# power.net
KiCad netlist of a schematic drawn in Altium Designer
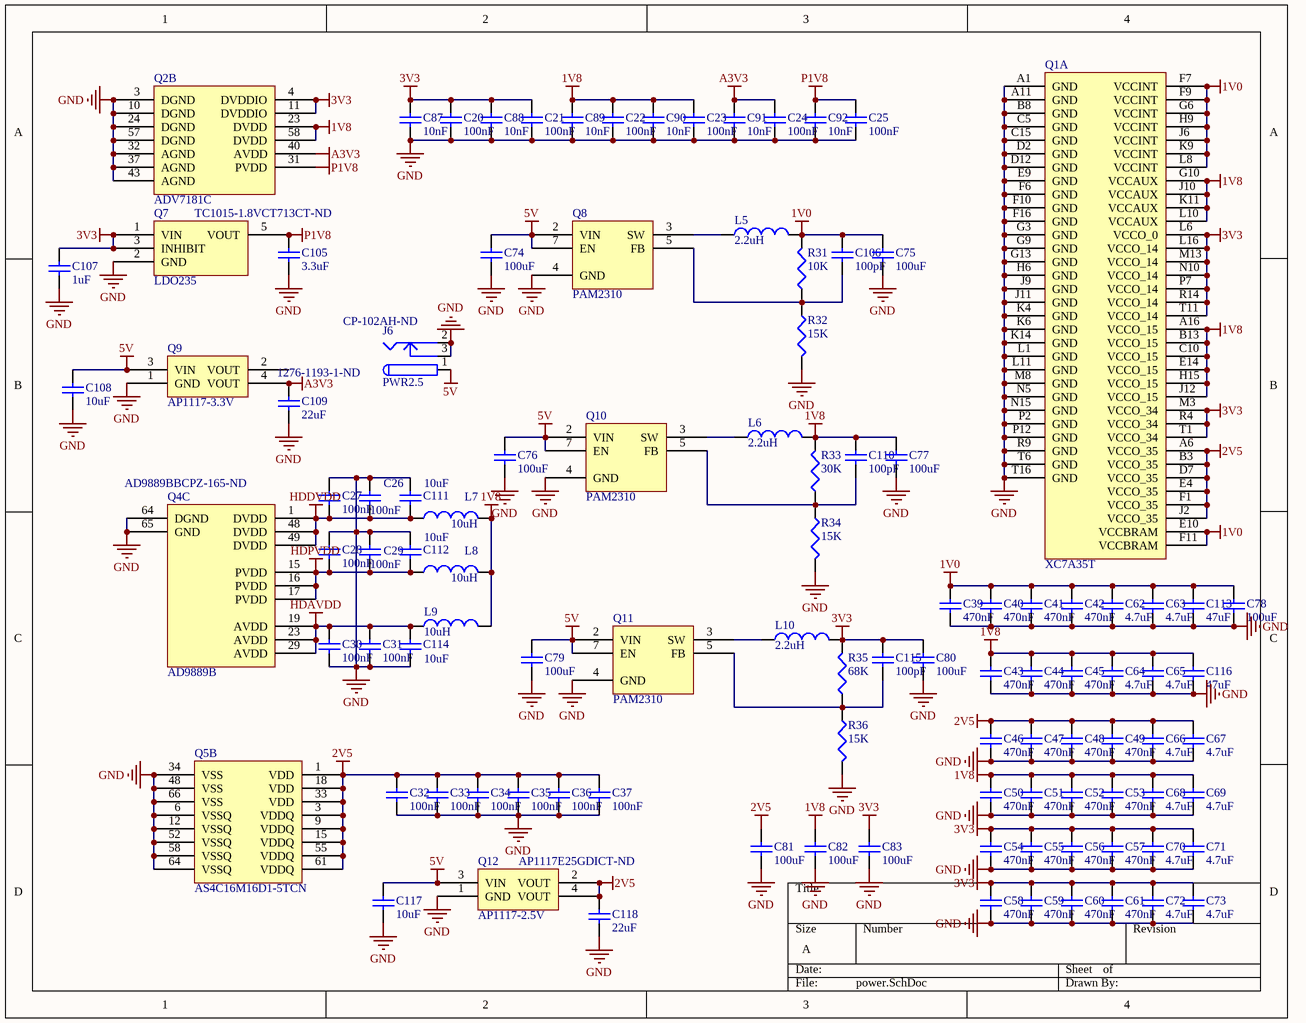
[diagram p0: power.SchDoc]

(export (version "E")
  (design (tool "Eeschema 10.0.6"))
  (components
    (comp (ref "C20")
      (value "100nF")
      (footprint "CAPC1005X06L")
      (description "Capacitor")
      (fields (field (name "Comment") "Cap") (field (name "PUBLISHER") "Altium Limited"))
      (libsource (lib "Miscellaneous Devices") (part "Cap"))
    )
    (comp (ref "C21")
      (value "100nF")
      (footprint "CAPC1005X06L")
      (description "Capacitor")
      (fields (field (name "Comment") "Cap") (field (name "PUBLISHER") "Altium Limited"))
      (libsource (lib "Miscellaneous Devices") (part "Cap"))
    )
    (comp (ref "C22")
      (value "100nF")
      (footprint "CAPC1005X06L")
      (description "Capacitor")
      (fields (field (name "Comment") "Cap") (field (name "PUBLISHER") "Altium Limited"))
      (libsource (lib "Miscellaneous Devices") (part "Cap"))
    )
    (comp (ref "C23")
      (value "100nF")
      (footprint "CAPC1005X06L")
      (description "Capacitor")
      (fields (field (name "Comment") "Cap") (field (name "PUBLISHER") "Altium Limited"))
      (libsource (lib "Miscellaneous Devices") (part "Cap"))
    )
    (comp (ref "C24")
      (value "100nF")
      (footprint "CAPC1005X06L")
      (description "Capacitor")
      (fields (field (name "Comment") "Cap") (field (name "PUBLISHER") "Altium Limited"))
      (libsource (lib "Miscellaneous Devices") (part "Cap"))
    )
    (comp (ref "C25")
      (value "100nF")
      (footprint "CAPC1005X06L")
      (description "Capacitor")
      (fields (field (name "Comment") "Cap") (field (name "PUBLISHER") "Altium Limited"))
      (libsource (lib "Miscellaneous Devices") (part "Cap"))
    )
    (comp (ref "C26")
      (value "100nF")
      (footprint "CAPC1005X06L")
      (description "Capacitor")
      (fields (field (name "Comment") "Cap") (field (name "PUBLISHER") "Altium Limited"))
      (libsource (lib "Miscellaneous Devices") (part "Cap"))
    )
    (comp (ref "C27")
      (value "100nF")
      (footprint "CAPC1005X06L")
      (description "Capacitor")
      (fields (field (name "Comment") "Cap") (field (name "PUBLISHER") "Altium Limited"))
      (libsource (lib "Miscellaneous Devices") (part "Cap"))
    )
    (comp (ref "C28")
      (value "100nF")
      (footprint "CAPC1005X06L")
      (description "Capacitor")
      (fields (field (name "Comment") "Cap") (field (name "PUBLISHER") "Altium Limited"))
      (libsource (lib "Miscellaneous Devices") (part "Cap"))
    )
    (comp (ref "C29")
      (value "100nF")
      (footprint "CAPC1005X06L")
      (description "Capacitor")
      (fields (field (name "Comment") "Cap") (field (name "PUBLISHER") "Altium Limited"))
      (libsource (lib "Miscellaneous Devices") (part "Cap"))
    )
    (comp (ref "C30")
      (value "100nF")
      (footprint "CAPC1005X06L")
      (description "Capacitor")
      (fields (field (name "Comment") "Cap") (field (name "PUBLISHER") "Altium Limited"))
      (libsource (lib "Miscellaneous Devices") (part "Cap"))
    )
    (comp (ref "C31")
      (value "100nF")
      (footprint "CAPC1005X06L")
      (description "Capacitor")
      (fields (field (name "Comment") "Cap") (field (name "PUBLISHER") "Altium Limited"))
      (libsource (lib "Miscellaneous Devices") (part "Cap"))
    )
    (comp (ref "C32")
      (value "100nF")
      (footprint "CAPC1005X06L")
      (description "Capacitor")
      (fields (field (name "Comment") "Cap") (field (name "PUBLISHER") "Altium Limited"))
      (libsource (lib "Miscellaneous Devices") (part "Cap"))
    )
    (comp (ref "C33")
      (value "100nF")
      (footprint "CAPC1005X06L")
      (description "Capacitor")
      (fields (field (name "Comment") "Cap") (field (name "PUBLISHER") "Altium Limited"))
      (libsource (lib "Miscellaneous Devices") (part "Cap"))
    )
    (comp (ref "C34")
      (value "100nF")
      (footprint "CAPC1005X06L")
      (description "Capacitor")
      (fields (field (name "Comment") "Cap") (field (name "PUBLISHER") "Altium Limited"))
      (libsource (lib "Miscellaneous Devices") (part "Cap"))
    )
    (comp (ref "C35")
      (value "100nF")
      (footprint "CAPC1005X06L")
      (description "Capacitor")
      (fields (field (name "Comment") "Cap") (field (name "PUBLISHER") "Altium Limited"))
      (libsource (lib "Miscellaneous Devices") (part "Cap"))
    )
    (comp (ref "C36")
      (value "100nF")
      (footprint "CAPC1005X06L")
      (description "Capacitor")
      (fields (field (name "Comment") "Cap") (field (name "PUBLISHER") "Altium Limited"))
      (libsource (lib "Miscellaneous Devices") (part "Cap"))
    )
    (comp (ref "C37")
      (value "100nF")
      (footprint "CAPC1005X06L")
      (description "Capacitor")
      (fields (field (name "Comment") "Cap") (field (name "PUBLISHER") "Altium Limited"))
      (libsource (lib "Miscellaneous Devices") (part "Cap"))
    )
    (comp (ref "C39")
      (value "470nF")
      (footprint "CAPC1005X06L")
      (description "Capacitor")
      (fields (field (name "Comment") "Cap") (field (name "PUBLISHER") "Altium Limited"))
      (libsource (lib "Miscellaneous Devices") (part "Cap"))
    )
    (comp (ref "C40")
      (value "470nF")
      (footprint "CAPC1005X06L")
      (description "Capacitor")
      (fields (field (name "Comment") "Cap") (field (name "PUBLISHER") "Altium Limited"))
      (libsource (lib "Miscellaneous Devices") (part "Cap"))
    )
    (comp (ref "C41")
      (value "470nF")
      (footprint "CAPC1005X06L")
      (description "Capacitor")
      (fields (field (name "Comment") "Cap") (field (name "PUBLISHER") "Altium Limited"))
      (libsource (lib "Miscellaneous Devices") (part "Cap"))
    )
    (comp (ref "C42")
      (value "470nF")
      (footprint "CAPC1005X06L")
      (description "Capacitor")
      (fields (field (name "Comment") "Cap") (field (name "PUBLISHER") "Altium Limited"))
      (libsource (lib "Miscellaneous Devices") (part "Cap"))
    )
    (comp (ref "C43")
      (value "470nF")
      (footprint "CAPC1005X06L")
      (description "Capacitor")
      (fields (field (name "Comment") "Cap") (field (name "PUBLISHER") "Altium Limited"))
      (libsource (lib "Miscellaneous Devices") (part "Cap"))
    )
    (comp (ref "C44")
      (value "470nF")
      (footprint "CAPC1005X06L")
      (description "Capacitor")
      (fields (field (name "Comment") "Cap") (field (name "PUBLISHER") "Altium Limited"))
      (libsource (lib "Miscellaneous Devices") (part "Cap"))
    )
    (comp (ref "C45")
      (value "470nF")
      (footprint "CAPC1005X06L")
      (description "Capacitor")
      (fields (field (name "Comment") "Cap") (field (name "PUBLISHER") "Altium Limited"))
      (libsource (lib "Miscellaneous Devices") (part "Cap"))
    )
    (comp (ref "C46")
      (value "470nF")
      (footprint "CAPC1005X06L")
      (description "Capacitor")
      (fields (field (name "Comment") "Cap") (field (name "PUBLISHER") "Altium Limited"))
      (libsource (lib "Miscellaneous Devices") (part "Cap"))
    )
    (comp (ref "C47")
      (value "470nF")
      (footprint "CAPC1005X06L")
      (description "Capacitor")
      (fields (field (name "Comment") "Cap") (field (name "PUBLISHER") "Altium Limited"))
      (libsource (lib "Miscellaneous Devices") (part "Cap"))
    )
    (comp (ref "C48")
      (value "470nF")
      (footprint "CAPC1005X06L")
      (description "Capacitor")
      (fields (field (name "Comment") "Cap") (field (name "PUBLISHER") "Altium Limited"))
      (libsource (lib "Miscellaneous Devices") (part "Cap"))
    )
    (comp (ref "C49")
      (value "470nF")
      (footprint "CAPC1005X06L")
      (description "Capacitor")
      (fields (field (name "Comment") "Cap") (field (name "PUBLISHER") "Altium Limited"))
      (libsource (lib "Miscellaneous Devices") (part "Cap"))
    )
    (comp (ref "C50")
      (value "470nF")
      (footprint "CAPC1005X06L")
      (description "Capacitor")
      (fields (field (name "Comment") "Cap") (field (name "PUBLISHER") "Altium Limited"))
      (libsource (lib "Miscellaneous Devices") (part "Cap"))
    )
    (comp (ref "C51")
      (value "470nF")
      (footprint "CAPC1005X06L")
      (description "Capacitor")
      (fields (field (name "Comment") "Cap") (field (name "PUBLISHER") "Altium Limited"))
      (libsource (lib "Miscellaneous Devices") (part "Cap"))
    )
    (comp (ref "C52")
      (value "470nF")
      (footprint "CAPC1005X06L")
      (description "Capacitor")
      (fields (field (name "Comment") "Cap") (field (name "PUBLISHER") "Altium Limited"))
      (libsource (lib "Miscellaneous Devices") (part "Cap"))
    )
    (comp (ref "C53")
      (value "470nF")
      (footprint "CAPC1005X06L")
      (description "Capacitor")
      (fields (field (name "Comment") "Cap") (field (name "PUBLISHER") "Altium Limited"))
      (libsource (lib "Miscellaneous Devices") (part "Cap"))
    )
    (comp (ref "C54")
      (value "470nF")
      (footprint "CAPC1005X06L")
      (description "Capacitor")
      (fields (field (name "Comment") "Cap") (field (name "PUBLISHER") "Altium Limited"))
      (libsource (lib "Miscellaneous Devices") (part "Cap"))
    )
    (comp (ref "C55")
      (value "470nF")
      (footprint "CAPC1005X06L")
      (description "Capacitor")
      (fields (field (name "Comment") "Cap") (field (name "PUBLISHER") "Altium Limited"))
      (libsource (lib "Miscellaneous Devices") (part "Cap"))
    )
    (comp (ref "C56")
      (value "470nF")
      (footprint "CAPC1005X06L")
      (description "Capacitor")
      (fields (field (name "Comment") "Cap") (field (name "PUBLISHER") "Altium Limited"))
      (libsource (lib "Miscellaneous Devices") (part "Cap"))
    )
    (comp (ref "C57")
      (value "470nF")
      (footprint "CAPC1005X06L")
      (description "Capacitor")
      (fields (field (name "Comment") "Cap") (field (name "PUBLISHER") "Altium Limited"))
      (libsource (lib "Miscellaneous Devices") (part "Cap"))
    )
    (comp (ref "C58")
      (value "470nF")
      (footprint "CAPC1005X06L")
      (description "Capacitor")
      (fields (field (name "Comment") "Cap") (field (name "PUBLISHER") "Altium Limited"))
      (libsource (lib "Miscellaneous Devices") (part "Cap"))
    )
    (comp (ref "C59")
      (value "470nF")
      (footprint "CAPC1005X06L")
      (description "Capacitor")
      (fields (field (name "Comment") "Cap") (field (name "PUBLISHER") "Altium Limited"))
      (libsource (lib "Miscellaneous Devices") (part "Cap"))
    )
    (comp (ref "C60")
      (value "470nF")
      (footprint "CAPC1005X06L")
      (description "Capacitor")
      (fields (field (name "Comment") "Cap") (field (name "PUBLISHER") "Altium Limited"))
      (libsource (lib "Miscellaneous Devices") (part "Cap"))
    )
    (comp (ref "C61")
      (value "470nF")
      (footprint "CAPC1005X06L")
      (description "Capacitor")
      (fields (field (name "Comment") "Cap") (field (name "PUBLISHER") "Altium Limited"))
      (libsource (lib "Miscellaneous Devices") (part "Cap"))
    )
    (comp (ref "C62")
      (value "4.7uF")
      (footprint "CAPC1608X90N")
      (description "Capacitor")
      (fields (field (name "Comment") "Cap") (field (name "PUBLISHER") "Altium Limited"))
      (libsource (lib "Miscellaneous Devices") (part "Cap"))
    )
    (comp (ref "C63")
      (value "4.7uF")
      (footprint "CAPC1608X90N")
      (description "Capacitor")
      (fields (field (name "Comment") "Cap") (field (name "PUBLISHER") "Altium Limited"))
      (libsource (lib "Miscellaneous Devices") (part "Cap"))
    )
    (comp (ref "C64")
      (value "4.7uF")
      (footprint "CAPC1608X90N")
      (description "Capacitor")
      (fields (field (name "Comment") "Cap") (field (name "PUBLISHER") "Altium Limited"))
      (libsource (lib "Miscellaneous Devices") (part "Cap"))
    )
    (comp (ref "C65")
      (value "4.7uF")
      (footprint "CAPC1608X90N")
      (description "Capacitor")
      (fields (field (name "Comment") "Cap") (field (name "PUBLISHER") "Altium Limited"))
      (libsource (lib "Miscellaneous Devices") (part "Cap"))
    )
    (comp (ref "C66")
      (value "4.7uF")
      (footprint "CAPC1608X90N")
      (description "Capacitor")
      (fields (field (name "Comment") "Cap") (field (name "PUBLISHER") "Altium Limited"))
      (libsource (lib "Miscellaneous Devices") (part "Cap"))
    )
    (comp (ref "C67")
      (value "4.7uF")
      (footprint "CAPC1608X90N")
      (description "Capacitor")
      (fields (field (name "Comment") "Cap") (field (name "PUBLISHER") "Altium Limited"))
      (libsource (lib "Miscellaneous Devices") (part "Cap"))
    )
    (comp (ref "C68")
      (value "4.7uF")
      (footprint "CAPC1608X90N")
      (description "Capacitor")
      (fields (field (name "Comment") "Cap") (field (name "PUBLISHER") "Altium Limited"))
      (libsource (lib "Miscellaneous Devices") (part "Cap"))
    )
    (comp (ref "C69")
      (value "4.7uF")
      (footprint "CAPC1608X90N")
      (description "Capacitor")
      (fields (field (name "Comment") "Cap") (field (name "PUBLISHER") "Altium Limited"))
      (libsource (lib "Miscellaneous Devices") (part "Cap"))
    )
    (comp (ref "C70")
      (value "4.7uF")
      (footprint "CAPC1608X90N")
      (description "Capacitor")
      (fields (field (name "Comment") "Cap") (field (name "PUBLISHER") "Altium Limited"))
      (libsource (lib "Miscellaneous Devices") (part "Cap"))
    )
    (comp (ref "C71")
      (value "4.7uF")
      (footprint "CAPC1608X90N")
      (description "Capacitor")
      (fields (field (name "Comment") "Cap") (field (name "PUBLISHER") "Altium Limited"))
      (libsource (lib "Miscellaneous Devices") (part "Cap"))
    )
    (comp (ref "C72")
      (value "4.7uF")
      (footprint "CAPC1608X90N")
      (description "Capacitor")
      (fields (field (name "Comment") "Cap") (field (name "PUBLISHER") "Altium Limited"))
      (libsource (lib "Miscellaneous Devices") (part "Cap"))
    )
    (comp (ref "C73")
      (value "4.7uF")
      (footprint "CAPC1608X90N")
      (description "Capacitor")
      (fields (field (name "Comment") "Cap") (field (name "PUBLISHER") "Altium Limited"))
      (libsource (lib "Miscellaneous Devices") (part "Cap"))
    )
    (comp (ref "C74")
      (value "100uF")
      (footprint "CAPC3216X100N")
      (description "Capacitor")
      (fields (field (name "Comment") "Cap") (field (name "PUBLISHER") "Altium Limited"))
      (libsource (lib "Miscellaneous Devices") (part "Cap"))
    )
    (comp (ref "C75")
      (value "100uF")
      (footprint "CAPC3216X100N")
      (description "Capacitor")
      (fields (field (name "Comment") "Cap") (field (name "PUBLISHER") "Altium Limited"))
      (libsource (lib "Miscellaneous Devices") (part "Cap"))
    )
    (comp (ref "C76")
      (value "100uF")
      (footprint "CAPC3216X100N")
      (description "Capacitor")
      (fields (field (name "Comment") "Cap") (field (name "PUBLISHER") "Altium Limited"))
      (libsource (lib "Miscellaneous Devices") (part "Cap"))
    )
    (comp (ref "C77")
      (value "100uF")
      (footprint "CAPC3216X100N")
      (description "Capacitor")
      (fields (field (name "Comment") "Cap") (field (name "PUBLISHER") "Altium Limited"))
      (libsource (lib "Miscellaneous Devices") (part "Cap"))
    )
    (comp (ref "C78")
      (value "100uF")
      (footprint "CAPC3216X100N")
      (description "Capacitor")
      (fields (field (name "Comment") "Cap") (field (name "PUBLISHER") "Altium Limited"))
      (libsource (lib "Miscellaneous Devices") (part "Cap"))
    )
    (comp (ref "C79")
      (value "100uF")
      (footprint "CAPC3216X100N")
      (description "Capacitor")
      (fields (field (name "Comment") "Cap") (field (name "PUBLISHER") "Altium Limited"))
      (libsource (lib "Miscellaneous Devices") (part "Cap"))
    )
    (comp (ref "C80")
      (value "100uF")
      (footprint "CAPC3216X100N")
      (description "Capacitor")
      (fields (field (name "Comment") "Cap") (field (name "PUBLISHER") "Altium Limited"))
      (libsource (lib "Miscellaneous Devices") (part "Cap"))
    )
    (comp (ref "C81")
      (value "100uF")
      (footprint "CAPC3216X100N")
      (description "Capacitor")
      (fields (field (name "Comment") "Cap") (field (name "PUBLISHER") "Altium Limited"))
      (libsource (lib "Miscellaneous Devices") (part "Cap"))
    )
    (comp (ref "C82")
      (value "100uF")
      (footprint "CAPC3216X100N")
      (description "Capacitor")
      (fields (field (name "Comment") "Cap") (field (name "PUBLISHER") "Altium Limited"))
      (libsource (lib "Miscellaneous Devices") (part "Cap"))
    )
    (comp (ref "C83")
      (value "100uF")
      (footprint "CAPC3216X100N")
      (description "Capacitor")
      (fields (field (name "Comment") "Cap") (field (name "PUBLISHER") "Altium Limited"))
      (libsource (lib "Miscellaneous Devices") (part "Cap"))
    )
    (comp (ref "C87")
      (value "10nF")
      (footprint "CAPC1005X06L")
      (description "Capacitor")
      (fields (field (name "Comment") "Cap") (field (name "PUBLISHER") "Altium Limited"))
      (libsource (lib "Miscellaneous Devices") (part "Cap"))
    )
    (comp (ref "C88")
      (value "10nF")
      (footprint "CAPC1005X06L")
      (description "Capacitor")
      (fields (field (name "Comment") "Cap") (field (name "PUBLISHER") "Altium Limited"))
      (libsource (lib "Miscellaneous Devices") (part "Cap"))
    )
    (comp (ref "C89")
      (value "10nF")
      (footprint "CAPC1005X06L")
      (description "Capacitor")
      (fields (field (name "Comment") "Cap") (field (name "PUBLISHER") "Altium Limited"))
      (libsource (lib "Miscellaneous Devices") (part "Cap"))
    )
    (comp (ref "C90")
      (value "10nF")
      (footprint "CAPC1005X06L")
      (description "Capacitor")
      (fields (field (name "Comment") "Cap") (field (name "PUBLISHER") "Altium Limited"))
      (libsource (lib "Miscellaneous Devices") (part "Cap"))
    )
    (comp (ref "C91")
      (value "10nF")
      (footprint "CAPC1005X06L")
      (description "Capacitor")
      (fields (field (name "Comment") "Cap") (field (name "PUBLISHER") "Altium Limited"))
      (libsource (lib "Miscellaneous Devices") (part "Cap"))
    )
    (comp (ref "C92")
      (value "10nF")
      (footprint "CAPC1005X06L")
      (description "Capacitor")
      (fields (field (name "Comment") "Cap") (field (name "PUBLISHER") "Altium Limited"))
      (libsource (lib "Miscellaneous Devices") (part "Cap"))
    )
    (comp (ref "C105")
      (value "3.3uF")
      (footprint "CAPC1608X90N")
      (description "Capacitor")
      (fields (field (name "Comment") "Cap") (field (name "PUBLISHER") "Altium Limited"))
      (libsource (lib "Miscellaneous Devices") (part "Cap"))
    )
    (comp (ref "C106")
      (value "100pF")
      (footprint "CAPC1608X90N")
      (description "Capacitor")
      (fields (field (name "Comment") "Cap") (field (name "PUBLISHER") "Altium Limited"))
      (libsource (lib "Miscellaneous Devices") (part "Cap"))
    )
    (comp (ref "C107")
      (value "1uF")
      (footprint "CAPC1608X90N")
      (description "Capacitor")
      (fields (field (name "Comment") "Cap") (field (name "PUBLISHER") "Altium Limited"))
      (libsource (lib "Miscellaneous Devices") (part "Cap"))
    )
    (comp (ref "C108")
      (value "10uF")
      (footprint "CAPC1608X90N")
      (description "Capacitor")
      (fields (field (name "Comment") "Cap") (field (name "PUBLISHER") "Altium Limited"))
      (libsource (lib "Miscellaneous Devices") (part "Cap"))
    )
    (comp (ref "C109")
      (value "22uF")
      (footprint "CAPC1608X90N")
      (description "Capacitor")
      (fields
        (field (name "SUPPLIER PART NUMBER 1") "1276-1193-1-ND")
        (field (name "Comment") "Cap")
        (field (name "PUBLISHER") "Altium Limited")
      )
      (libsource (lib "Miscellaneous Devices") (part "Cap"))
    )
    (comp (ref "C110")
      (value "100pF")
      (footprint "CAPC1608X90N")
      (description "Capacitor")
      (fields (field (name "Comment") "Cap") (field (name "PUBLISHER") "Altium Limited"))
      (libsource (lib "Miscellaneous Devices") (part "Cap"))
    )
    (comp (ref "C111")
      (value "10uF")
      (footprint "CAPC1608X90N")
      (description "Capacitor")
      (fields (field (name "Comment") "Cap") (field (name "PUBLISHER") "Altium Limited"))
      (libsource (lib "Miscellaneous Devices") (part "Cap"))
    )
    (comp (ref "C112")
      (value "10uF")
      (footprint "CAPC1608X90N")
      (description "Capacitor")
      (fields (field (name "Comment") "Cap") (field (name "PUBLISHER") "Altium Limited"))
      (libsource (lib "Miscellaneous Devices") (part "Cap"))
    )
    (comp (ref "C113")
      (value "47uF")
      (footprint "CAPC2012X135N")
      (description "Capacitor")
      (fields (field (name "Comment") "Cap") (field (name "PUBLISHER") "Altium Limited"))
      (libsource (lib "Miscellaneous Devices") (part "Cap"))
    )
    (comp (ref "C114")
      (value "10uF")
      (footprint "CAPC1608X90N")
      (description "Capacitor")
      (fields (field (name "Comment") "Cap") (field (name "PUBLISHER") "Altium Limited"))
      (libsource (lib "Miscellaneous Devices") (part "Cap"))
    )
    (comp (ref "C115")
      (value "100pF")
      (footprint "CAPC1608X90N")
      (description "Capacitor")
      (fields (field (name "Comment") "Cap") (field (name "PUBLISHER") "Altium Limited"))
      (libsource (lib "Miscellaneous Devices") (part "Cap"))
    )
    (comp (ref "C116")
      (value "47uF")
      (footprint "CAPC2012X135N")
      (description "Capacitor")
      (fields (field (name "Comment") "Cap") (field (name "PUBLISHER") "Altium Limited"))
      (libsource (lib "Miscellaneous Devices") (part "Cap"))
    )
    (comp (ref "C117")
      (value "10uF")
      (footprint "CAPC1608X90N")
      (description "Capacitor")
      (fields (field (name "Comment") "Cap") (field (name "PUBLISHER") "Altium Limited"))
      (libsource (lib "Miscellaneous Devices") (part "Cap"))
    )
    (comp (ref "C118")
      (value "22uF")
      (footprint "CAPC1608X90N")
      (description "Capacitor")
      (fields (field (name "Comment") "Cap") (field (name "PUBLISHER") "Altium Limited"))
      (libsource (lib "Miscellaneous Devices") (part "Cap"))
    )
    (comp (ref "J6")
      (value "PWR2.5")
      (footprint "PJ-102A")
      (description "Low Voltage Power Supply Connector")
      (fields
        (field (name "SUPPLIER PART NUMBER 1") "CP-102AH-ND")
        (field (name "PUBLISHER") "Altium Limited")
      )
      (libsource (lib "Miscellaneous Connectors") (part "PWR2.5"))
    )
    (comp (ref "L5")
      (value "2.2uH")
      (footprint "NRS8030T2R2NJGJ")
      (description "Inductor")
      (fields (field (name "Comment") "NRS8030T2R2NJGJ") (field (name "PUBLISHER") "Altium Limited"))
      (libsource (lib "Miscellaneous Devices") (part "Inductor"))
    )
    (comp (ref "L6")
      (value "2.2uH")
      (footprint "NRS8030T2R2NJGJ")
      (description "Inductor")
      (fields (field (name "Comment") "NRS8030T2R2NJGJ") (field (name "PUBLISHER") "Altium Limited"))
      (libsource (lib "Miscellaneous Devices") (part "Inductor"))
    )
    (comp (ref "L7")
      (value "10uH")
      (footprint "CAPC3225X220N")
      (description "Inductor")
      (fields (field (name "Comment") "LBC3225T100KR") (field (name "PUBLISHER") "Altium Limited"))
      (libsource (lib "Miscellaneous Devices") (part "Inductor"))
    )
    (comp (ref "L8")
      (value "10uH")
      (footprint "CAPC3225X220N")
      (description "Inductor")
      (fields (field (name "Comment") "LBC3225T100KR") (field (name "PUBLISHER") "Altium Limited"))
      (libsource (lib "Miscellaneous Devices") (part "Inductor"))
    )
    (comp (ref "L9")
      (value "10uH")
      (footprint "CAPC3225X220N")
      (description "Inductor")
      (fields (field (name "Comment") "LBC3225T100KR") (field (name "PUBLISHER") "Altium Limited"))
      (libsource (lib "Miscellaneous Devices") (part "Inductor"))
    )
    (comp (ref "L10")
      (value "2.2uH")
      (footprint "NRS8030T2R2NJGJ")
      (description "Inductor")
      (fields (field (name "Comment") "NRS8030T2R2NJGJ") (field (name "PUBLISHER") "Altium Limited"))
      (libsource (lib "Miscellaneous Devices") (part "Inductor"))
    )
    (comp (ref "Q1") (value "XC7A35T") (libsource (lib "schlib") (part "XC7A35T")))
    (comp (ref "Q2")
      (value "ADV7181C")
      (footprint "TSQFP50P1200X1200X145-64N")
      (libsource (lib "schlib") (part "ADV7181C"))
    )
    (comp (ref "Q4")
      (value "AD9889B")
      (footprint "QFN50P900X875X100_HS-65N")
      (fields (field (name "SUPPLIER PART NUMBER 1") "AD9889BBCPZ-165-ND"))
      (libsource (lib "schlib") (part "AD9889B"))
    )
    (comp (ref "Q5")
      (value "AS4C16M16D1-5TCN")
      (footprint "TSOP65P1180X120-66N")
      (libsource (lib "schlib") (part "DDR256"))
    )
    (comp (ref "Q7")
      (value "LDO235")
      (footprint "SOT23-5")
      (fields (field (name "SUPPLIER PART NUMBER 1") "TC1015-1.8VCT713CT-ND"))
      (libsource (lib "schlib") (part "LDO235"))
    )
    (comp (ref "Q8")
      (value "PAM2310")
      (footprint "SOIC127P600X175-8AN")
      (libsource (lib "schlib") (part "PAM2310"))
    )
    (comp (ref "Q9") (value "AP1117-3.3V") (footprint "SOT223") (libsource (lib "schlib") (part "AP1117")))
    (comp (ref "Q10")
      (value "PAM2310")
      (footprint "SOIC127P600X175-8AN")
      (libsource (lib "schlib") (part "PAM2310"))
    )
    (comp (ref "Q11")
      (value "PAM2310")
      (footprint "SOIC127P600X175-8AN")
      (libsource (lib "schlib") (part "PAM2310"))
    )
    (comp (ref "Q12")
      (value "AP1117-2.5V")
      (footprint "SOT223")
      (fields (field (name "SUPPLIER PART NUMBER 1") "AP1117E25GDICT-ND"))
      (libsource (lib "schlib") (part "AP1117"))
    )
    (comp (ref "R31")
      (value "10K")
      (footprint "CAPC1608X90N")
      (description "Resistor")
      (fields (field (name "Comment") "Res3") (field (name "PUBLISHER") "Altium Limited"))
      (libsource (lib "Miscellaneous Devices") (part "Res3"))
    )
    (comp (ref "R32")
      (value "15K")
      (footprint "CAPC1608X90N")
      (description "Resistor")
      (fields (field (name "Comment") "Res3") (field (name "PUBLISHER") "Altium Limited"))
      (libsource (lib "Miscellaneous Devices") (part "Res3"))
    )
    (comp (ref "R33")
      (value "30K")
      (footprint "CAPC1608X90N")
      (description "Resistor")
      (fields (field (name "Comment") "Res3") (field (name "PUBLISHER") "Altium Limited"))
      (libsource (lib "Miscellaneous Devices") (part "Res3"))
    )
    (comp (ref "R34")
      (value "15K")
      (footprint "CAPC1608X90N")
      (description "Resistor")
      (fields (field (name "Comment") "Res3") (field (name "PUBLISHER") "Altium Limited"))
      (libsource (lib "Miscellaneous Devices") (part "Res3"))
    )
    (comp (ref "R35")
      (value "68K")
      (footprint "CAPC1608X90N")
      (description "Resistor")
      (fields (field (name "Comment") "Res3") (field (name "PUBLISHER") "Altium Limited"))
      (libsource (lib "Miscellaneous Devices") (part "Res3"))
    )
    (comp (ref "R36")
      (value "15K")
      (footprint "CAPC1608X90N")
      (description "Resistor")
      (fields (field (name "Comment") "Res3") (field (name "PUBLISHER") "Altium Limited"))
      (libsource (lib "Miscellaneous Devices") (part "Res3"))
    )
  )
  (nets
    (net (code "1") (name "1V0") (class "Default")
      (node (ref "C106") (pin "1") (pinfunction "1_1") (pintype "passive"))
      (node (ref "C113") (pin "1") (pinfunction "1_1") (pintype "passive"))
      (node (ref "C39") (pin "2") (pinfunction "2_2") (pintype "passive"))
      (node (ref "C40") (pin "2") (pinfunction "2_2") (pintype "passive"))
      (node (ref "C41") (pin "2") (pinfunction "2_2") (pintype "passive"))
      (node (ref "C42") (pin "2") (pinfunction "2_2") (pintype "passive"))
      (node (ref "C62") (pin "1") (pinfunction "1_1") (pintype "passive"))
      (node (ref "C63") (pin "1") (pinfunction "1_1") (pintype "passive"))
      (node (ref "C75") (pin "1") (pinfunction "1_1") (pintype "passive"))
      (node (ref "C78") (pin "1") (pinfunction "1_1") (pintype "passive"))
      (node (ref "L5") (pin "2") (pinfunction "2_2") (pintype "passive"))
      (node (ref "Q1") (pin "E10") (pinfunction "VCCBRAM_E10") (pintype "passive"))
      (node (ref "Q1") (pin "F11") (pinfunction "VCCBRAM_F11") (pintype "passive"))
      (node (ref "Q1") (pin "F7") (pinfunction "VCCINT_F7") (pintype "passive"))
      (node (ref "Q1") (pin "F9") (pinfunction "VCCINT_F9") (pintype "passive"))
      (node (ref "Q1") (pin "G6") (pinfunction "VCCINT_G6") (pintype "passive"))
      (node (ref "Q1") (pin "H9") (pinfunction "VCCINT_H9") (pintype "passive"))
      (node (ref "Q1") (pin "J6") (pinfunction "VCCINT_J6") (pintype "passive"))
      (node (ref "Q1") (pin "K9") (pinfunction "VCCINT_K9") (pintype "passive"))
      (node (ref "Q1") (pin "L8") (pinfunction "VCCINT_L8") (pintype "passive"))
      (node (ref "R31") (pin "2") (pinfunction "2_2") (pintype "passive"))
    )
    (net (code "2") (name "1V8") (class "Default")
      (node (ref "C110") (pin "1") (pinfunction "1_1") (pintype "passive"))
      (node (ref "C116") (pin "1") (pinfunction "1_1") (pintype "passive"))
      (node (ref "C22") (pin "2") (pinfunction "2_2") (pintype "passive"))
      (node (ref "C23") (pin "2") (pinfunction "2_2") (pintype "passive"))
      (node (ref "C43") (pin "2") (pinfunction "2_2") (pintype "passive"))
      (node (ref "C44") (pin "2") (pinfunction "2_2") (pintype "passive"))
      (node (ref "C45") (pin "2") (pinfunction "2_2") (pintype "passive"))
      (node (ref "C50") (pin "2") (pinfunction "2_2") (pintype "passive"))
      (node (ref "C51") (pin "2") (pinfunction "2_2") (pintype "passive"))
      (node (ref "C52") (pin "2") (pinfunction "2_2") (pintype "passive"))
      (node (ref "C53") (pin "2") (pinfunction "2_2") (pintype "passive"))
      (node (ref "C64") (pin "1") (pinfunction "1_1") (pintype "passive"))
      (node (ref "C65") (pin "1") (pinfunction "1_1") (pintype "passive"))
      (node (ref "C68") (pin "1") (pinfunction "1_1") (pintype "passive"))
      (node (ref "C69") (pin "1") (pinfunction "1_1") (pintype "passive"))
      (node (ref "C77") (pin "1") (pinfunction "1_1") (pintype "passive"))
      (node (ref "C82") (pin "1") (pinfunction "1_1") (pintype "passive"))
      (node (ref "C89") (pin "2") (pinfunction "2_2") (pintype "passive"))
      (node (ref "C90") (pin "2") (pinfunction "2_2") (pintype "passive"))
      (node (ref "L6") (pin "2") (pinfunction "2_2") (pintype "passive"))
      (node (ref "L7") (pin "2") (pinfunction "2_2") (pintype "passive"))
      (node (ref "L8") (pin "2") (pinfunction "2_2") (pintype "passive"))
      (node (ref "L9") (pin "2") (pinfunction "2_2") (pintype "passive"))
      (node (ref "Q1") (pin "A16") (pinfunction "VCCO_15_A16") (pintype "passive"))
      (node (ref "Q1") (pin "B13") (pinfunction "VCCO_15_B13") (pintype "passive"))
      (node (ref "Q1") (pin "C10") (pinfunction "VCCO_15_C10") (pintype "passive"))
      (node (ref "Q1") (pin "E14") (pinfunction "VCCO_15_E14") (pintype "passive"))
      (node (ref "Q1") (pin "G10") (pinfunction "VCCAUX_G10") (pintype "passive"))
      (node (ref "Q1") (pin "H15") (pinfunction "VCCO_15_H15") (pintype "passive"))
      (node (ref "Q1") (pin "J10") (pinfunction "VCCAUX_J10") (pintype "passive"))
      (node (ref "Q1") (pin "J12") (pinfunction "VCCO_15_J12") (pintype "passive"))
      (node (ref "Q1") (pin "K11") (pinfunction "VCCAUX_K11") (pintype "passive"))
      (node (ref "Q1") (pin "L10") (pinfunction "VCCAUX_L10") (pintype "passive"))
      (node (ref "Q2") (pin "23") (pinfunction "DVDD_23") (pintype "passive"))
      (node (ref "Q2") (pin "58") (pinfunction "DVDD_58") (pintype "passive"))
      (node (ref "R33") (pin "2") (pinfunction "2_2") (pintype "passive"))
    )
    (net (code "3") (name "2V5") (class "Default")
      (node (ref "C118") (pin "1") (pinfunction "1_1") (pintype "passive"))
      (node (ref "C32") (pin "2") (pinfunction "2_2") (pintype "passive"))
      (node (ref "C33") (pin "2") (pinfunction "2_2") (pintype "passive"))
      (node (ref "C34") (pin "2") (pinfunction "2_2") (pintype "passive"))
      (node (ref "C35") (pin "2") (pinfunction "2_2") (pintype "passive"))
      (node (ref "C36") (pin "2") (pinfunction "2_2") (pintype "passive"))
      (node (ref "C37") (pin "2") (pinfunction "2_2") (pintype "passive"))
      (node (ref "C46") (pin "2") (pinfunction "2_2") (pintype "passive"))
      (node (ref "C47") (pin "2") (pinfunction "2_2") (pintype "passive"))
      (node (ref "C48") (pin "2") (pinfunction "2_2") (pintype "passive"))
      (node (ref "C49") (pin "2") (pinfunction "2_2") (pintype "passive"))
      (node (ref "C66") (pin "1") (pinfunction "1_1") (pintype "passive"))
      (node (ref "C67") (pin "1") (pinfunction "1_1") (pintype "passive"))
      (node (ref "C81") (pin "1") (pinfunction "1_1") (pintype "passive"))
      (node (ref "Q1") (pin "A6") (pinfunction "VCCO_35_A6") (pintype "passive"))
      (node (ref "Q1") (pin "B3") (pinfunction "VCCO_35_B3") (pintype "passive"))
      (node (ref "Q1") (pin "D7") (pinfunction "VCCO_35_D7") (pintype "passive"))
      (node (ref "Q1") (pin "E4") (pinfunction "VCCO_35_E4") (pintype "passive"))
      (node (ref "Q1") (pin "F1") (pinfunction "VCCO_35_F1") (pintype "passive"))
      (node (ref "Q1") (pin "J2") (pinfunction "VCCO_35_J2") (pintype "passive"))
      (node (ref "Q12") (pin "2") (pinfunction "VOUT_2") (pintype "passive"))
      (node (ref "Q12") (pin "4") (pinfunction "VOUT_4") (pintype "passive"))
      (node (ref "Q5") (pin "1") (pinfunction "VDD_1") (pintype "passive"))
      (node (ref "Q5") (pin "15") (pinfunction "VDDQ_15") (pintype "passive"))
      (node (ref "Q5") (pin "18") (pinfunction "VDD_18") (pintype "passive"))
      (node (ref "Q5") (pin "3") (pinfunction "VDDQ_3") (pintype "passive"))
      (node (ref "Q5") (pin "33") (pinfunction "VDD_33") (pintype "passive"))
      (node (ref "Q5") (pin "55") (pinfunction "VDDQ_55") (pintype "passive"))
      (node (ref "Q5") (pin "61") (pinfunction "VDDQ_61") (pintype "passive"))
      (node (ref "Q5") (pin "9") (pinfunction "VDDQ_9") (pintype "passive"))
    )
    (net (code "4") (name "3V3") (class "Default")
      (node (ref "C107") (pin "1") (pinfunction "1_1") (pintype "passive"))
      (node (ref "C115") (pin "1") (pinfunction "1_1") (pintype "passive"))
      (node (ref "C20") (pin "2") (pinfunction "2_2") (pintype "passive"))
      (node (ref "C21") (pin "2") (pinfunction "2_2") (pintype "passive"))
      (node (ref "C54") (pin "2") (pinfunction "2_2") (pintype "passive"))
      (node (ref "C55") (pin "2") (pinfunction "2_2") (pintype "passive"))
      (node (ref "C56") (pin "2") (pinfunction "2_2") (pintype "passive"))
      (node (ref "C57") (pin "2") (pinfunction "2_2") (pintype "passive"))
      (node (ref "C58") (pin "2") (pinfunction "2_2") (pintype "passive"))
      (node (ref "C59") (pin "2") (pinfunction "2_2") (pintype "passive"))
      (node (ref "C60") (pin "2") (pinfunction "2_2") (pintype "passive"))
      (node (ref "C61") (pin "2") (pinfunction "2_2") (pintype "passive"))
      (node (ref "C70") (pin "1") (pinfunction "1_1") (pintype "passive"))
      (node (ref "C71") (pin "1") (pinfunction "1_1") (pintype "passive"))
      (node (ref "C72") (pin "1") (pinfunction "1_1") (pintype "passive"))
      (node (ref "C73") (pin "1") (pinfunction "1_1") (pintype "passive"))
      (node (ref "C80") (pin "1") (pinfunction "1_1") (pintype "passive"))
      (node (ref "C83") (pin "1") (pinfunction "1_1") (pintype "passive"))
      (node (ref "C87") (pin "2") (pinfunction "2_2") (pintype "passive"))
      (node (ref "C88") (pin "2") (pinfunction "2_2") (pintype "passive"))
      (node (ref "L10") (pin "2") (pinfunction "2_2") (pintype "passive"))
      (node (ref "Q1") (pin "L16") (pinfunction "VCCO_14_L16") (pintype "passive"))
      (node (ref "Q1") (pin "L6") (pinfunction "VCCO_0_L6") (pintype "passive"))
      (node (ref "Q1") (pin "M13") (pinfunction "VCCO_14_M13") (pintype "passive"))
      (node (ref "Q1") (pin "M3") (pinfunction "VCCO_34_M3") (pintype "passive"))
      (node (ref "Q1") (pin "N10") (pinfunction "VCCO_14_N10") (pintype "passive"))
      (node (ref "Q1") (pin "P7") (pinfunction "VCCO_14_P7") (pintype "passive"))
      (node (ref "Q1") (pin "R14") (pinfunction "VCCO_14_R14") (pintype "passive"))
      (node (ref "Q1") (pin "R4") (pinfunction "VCCO_34_R4") (pintype "passive"))
      (node (ref "Q1") (pin "T1") (pinfunction "VCCO_34_T1") (pintype "passive"))
      (node (ref "Q1") (pin "T11") (pinfunction "VCCO_14_T11") (pintype "passive"))
      (node (ref "Q2") (pin "11") (pinfunction "DVDDIO_11") (pintype "passive"))
      (node (ref "Q2") (pin "4") (pinfunction "DVDDIO_4") (pintype "passive"))
      (node (ref "Q7") (pin "1") (pinfunction "VIN_1") (pintype "passive"))
      (node (ref "Q7") (pin "3") (pinfunction "INHIBIT_3") (pintype "passive"))
      (node (ref "R35") (pin "2") (pinfunction "2_2") (pintype "passive"))
    )
    (net (code "5") (name "5V") (class "Default")
      (node (ref "C108") (pin "1") (pinfunction "1_1") (pintype "passive"))
      (node (ref "C117") (pin "1") (pinfunction "1_1") (pintype "passive"))
      (node (ref "C74") (pin "1") (pinfunction "1_1") (pintype "passive"))
      (node (ref "C76") (pin "1") (pinfunction "1_1") (pintype "passive"))
      (node (ref "C79") (pin "1") (pinfunction "1_1") (pintype "passive"))
      (node (ref "J6") (pin "1") (pinfunction "1_1") (pintype "power_in"))
      (node (ref "Q10") (pin "2") (pinfunction "VIN_2") (pintype "passive"))
      (node (ref "Q10") (pin "7") (pinfunction "EN_7") (pintype "passive"))
      (node (ref "Q11") (pin "2") (pinfunction "VIN_2") (pintype "passive"))
      (node (ref "Q11") (pin "7") (pinfunction "EN_7") (pintype "passive"))
      (node (ref "Q12") (pin "3") (pinfunction "VIN_3") (pintype "passive"))
      (node (ref "Q8") (pin "2") (pinfunction "VIN_2") (pintype "passive"))
      (node (ref "Q8") (pin "7") (pinfunction "EN_7") (pintype "passive"))
      (node (ref "Q9") (pin "3") (pinfunction "VIN_3") (pintype "passive"))
    )
    (net (code "6") (name "A3V3") (class "Default")
      (node (ref "C109") (pin "1") (pinfunction "1_1") (pintype "passive"))
      (node (ref "C24") (pin "2") (pinfunction "2_2") (pintype "passive"))
      (node (ref "C91") (pin "2") (pinfunction "2_2") (pintype "passive"))
      (node (ref "Q2") (pin "40") (pinfunction "AVDD_40") (pintype "passive"))
      (node (ref "Q9") (pin "4") (pinfunction "VOUT_4") (pintype "passive"))
    )
    (net (code "7") (name "GND") (class "Default")
      (node (ref "C105") (pin "2") (pinfunction "2_2") (pintype "passive"))
      (node (ref "C107") (pin "2") (pinfunction "2_2") (pintype "passive"))
      (node (ref "C108") (pin "2") (pinfunction "2_2") (pintype "passive"))
      (node (ref "C109") (pin "2") (pinfunction "2_2") (pintype "passive"))
      (node (ref "C111") (pin "1") (pinfunction "1_1") (pintype "passive"))
      (node (ref "C112") (pin "1") (pinfunction "1_1") (pintype "passive"))
      (node (ref "C113") (pin "2") (pinfunction "2_2") (pintype "passive"))
      (node (ref "C114") (pin "2") (pinfunction "2_2") (pintype "passive"))
      (node (ref "C116") (pin "2") (pinfunction "2_2") (pintype "passive"))
      (node (ref "C117") (pin "2") (pinfunction "2_2") (pintype "passive"))
      (node (ref "C118") (pin "2") (pinfunction "2_2") (pintype "passive"))
      (node (ref "C20") (pin "1") (pinfunction "1_1") (pintype "passive"))
      (node (ref "C21") (pin "1") (pinfunction "1_1") (pintype "passive"))
      (node (ref "C22") (pin "1") (pinfunction "1_1") (pintype "passive"))
      (node (ref "C23") (pin "1") (pinfunction "1_1") (pintype "passive"))
      (node (ref "C24") (pin "1") (pinfunction "1_1") (pintype "passive"))
      (node (ref "C25") (pin "1") (pinfunction "1_1") (pintype "passive"))
      (node (ref "C26") (pin "2") (pinfunction "2_2") (pintype "passive"))
      (node (ref "C27") (pin "2") (pinfunction "2_2") (pintype "passive"))
      (node (ref "C28") (pin "2") (pinfunction "2_2") (pintype "passive"))
      (node (ref "C29") (pin "2") (pinfunction "2_2") (pintype "passive"))
      (node (ref "C30") (pin "1") (pinfunction "1_1") (pintype "passive"))
      (node (ref "C31") (pin "1") (pinfunction "1_1") (pintype "passive"))
      (node (ref "C32") (pin "1") (pinfunction "1_1") (pintype "passive"))
      (node (ref "C33") (pin "1") (pinfunction "1_1") (pintype "passive"))
      (node (ref "C34") (pin "1") (pinfunction "1_1") (pintype "passive"))
      (node (ref "C35") (pin "1") (pinfunction "1_1") (pintype "passive"))
      (node (ref "C36") (pin "1") (pinfunction "1_1") (pintype "passive"))
      (node (ref "C37") (pin "1") (pinfunction "1_1") (pintype "passive"))
      (node (ref "C39") (pin "1") (pinfunction "1_1") (pintype "passive"))
      (node (ref "C40") (pin "1") (pinfunction "1_1") (pintype "passive"))
      (node (ref "C41") (pin "1") (pinfunction "1_1") (pintype "passive"))
      (node (ref "C42") (pin "1") (pinfunction "1_1") (pintype "passive"))
      (node (ref "C43") (pin "1") (pinfunction "1_1") (pintype "passive"))
      (node (ref "C44") (pin "1") (pinfunction "1_1") (pintype "passive"))
      (node (ref "C45") (pin "1") (pinfunction "1_1") (pintype "passive"))
      (node (ref "C46") (pin "1") (pinfunction "1_1") (pintype "passive"))
      (node (ref "C47") (pin "1") (pinfunction "1_1") (pintype "passive"))
      (node (ref "C48") (pin "1") (pinfunction "1_1") (pintype "passive"))
      (node (ref "C49") (pin "1") (pinfunction "1_1") (pintype "passive"))
      (node (ref "C50") (pin "1") (pinfunction "1_1") (pintype "passive"))
      (node (ref "C51") (pin "1") (pinfunction "1_1") (pintype "passive"))
      (node (ref "C52") (pin "1") (pinfunction "1_1") (pintype "passive"))
      (node (ref "C53") (pin "1") (pinfunction "1_1") (pintype "passive"))
      (node (ref "C54") (pin "1") (pinfunction "1_1") (pintype "passive"))
      (node (ref "C55") (pin "1") (pinfunction "1_1") (pintype "passive"))
      (node (ref "C56") (pin "1") (pinfunction "1_1") (pintype "passive"))
      (node (ref "C57") (pin "1") (pinfunction "1_1") (pintype "passive"))
      (node (ref "C58") (pin "1") (pinfunction "1_1") (pintype "passive"))
      (node (ref "C59") (pin "1") (pinfunction "1_1") (pintype "passive"))
      (node (ref "C60") (pin "1") (pinfunction "1_1") (pintype "passive"))
      (node (ref "C61") (pin "1") (pinfunction "1_1") (pintype "passive"))
      (node (ref "C62") (pin "2") (pinfunction "2_2") (pintype "passive"))
      (node (ref "C63") (pin "2") (pinfunction "2_2") (pintype "passive"))
      (node (ref "C64") (pin "2") (pinfunction "2_2") (pintype "passive"))
      (node (ref "C65") (pin "2") (pinfunction "2_2") (pintype "passive"))
      (node (ref "C66") (pin "2") (pinfunction "2_2") (pintype "passive"))
      (node (ref "C67") (pin "2") (pinfunction "2_2") (pintype "passive"))
      (node (ref "C68") (pin "2") (pinfunction "2_2") (pintype "passive"))
      (node (ref "C69") (pin "2") (pinfunction "2_2") (pintype "passive"))
      (node (ref "C70") (pin "2") (pinfunction "2_2") (pintype "passive"))
      (node (ref "C71") (pin "2") (pinfunction "2_2") (pintype "passive"))
      (node (ref "C72") (pin "2") (pinfunction "2_2") (pintype "passive"))
      (node (ref "C73") (pin "2") (pinfunction "2_2") (pintype "passive"))
      (node (ref "C74") (pin "2") (pinfunction "2_2") (pintype "passive"))
      (node (ref "C75") (pin "2") (pinfunction "2_2") (pintype "passive"))
      (node (ref "C76") (pin "2") (pinfunction "2_2") (pintype "passive"))
      (node (ref "C77") (pin "2") (pinfunction "2_2") (pintype "passive"))
      (node (ref "C78") (pin "2") (pinfunction "2_2") (pintype "passive"))
      (node (ref "C79") (pin "2") (pinfunction "2_2") (pintype "passive"))
      (node (ref "C80") (pin "2") (pinfunction "2_2") (pintype "passive"))
      (node (ref "C81") (pin "2") (pinfunction "2_2") (pintype "passive"))
      (node (ref "C82") (pin "2") (pinfunction "2_2") (pintype "passive"))
      (node (ref "C83") (pin "2") (pinfunction "2_2") (pintype "passive"))
      (node (ref "C87") (pin "1") (pinfunction "1_1") (pintype "passive"))
      (node (ref "C88") (pin "1") (pinfunction "1_1") (pintype "passive"))
      (node (ref "C89") (pin "1") (pinfunction "1_1") (pintype "passive"))
      (node (ref "C90") (pin "1") (pinfunction "1_1") (pintype "passive"))
      (node (ref "C91") (pin "1") (pinfunction "1_1") (pintype "passive"))
      (node (ref "C92") (pin "1") (pinfunction "1_1") (pintype "passive"))
      (node (ref "J6") (pin "2") (pinfunction "2_2") (pintype "power_in"))
      (node (ref "J6") (pin "3") (pinfunction "3_3") (pintype "power_in"))
      (node (ref "Q1") (pin "A1") (pinfunction "GND_A1") (pintype "passive"))
      (node (ref "Q1") (pin "A11") (pinfunction "GND_A11") (pintype "passive"))
      (node (ref "Q1") (pin "B8") (pinfunction "GND_B8") (pintype "passive"))
      (node (ref "Q1") (pin "C15") (pinfunction "GND_C15") (pintype "passive"))
      (node (ref "Q1") (pin "C5") (pinfunction "GND_C5") (pintype "passive"))
      (node (ref "Q1") (pin "D12") (pinfunction "GND_D12") (pintype "passive"))
      (node (ref "Q1") (pin "D2") (pinfunction "GND_D2") (pintype "passive"))
      (node (ref "Q1") (pin "E9") (pinfunction "GND_E9") (pintype "passive"))
      (node (ref "Q1") (pin "F10") (pinfunction "GND_F10") (pintype "passive"))
      (node (ref "Q1") (pin "F16") (pinfunction "GND_F16") (pintype "passive"))
      (node (ref "Q1") (pin "F6") (pinfunction "GND_F6") (pintype "passive"))
      (node (ref "Q1") (pin "G13") (pinfunction "GND_G13") (pintype "passive"))
      (node (ref "Q1") (pin "G3") (pinfunction "GND_G3") (pintype "passive"))
      (node (ref "Q1") (pin "G9") (pinfunction "GND_G9") (pintype "passive"))
      (node (ref "Q1") (pin "H6") (pinfunction "GND_H6") (pintype "passive"))
      (node (ref "Q1") (pin "J11") (pinfunction "GND_J11") (pintype "passive"))
      (node (ref "Q1") (pin "J9") (pinfunction "GND_J9") (pintype "passive"))
      (node (ref "Q1") (pin "K14") (pinfunction "GND_K14") (pintype "passive"))
      (node (ref "Q1") (pin "K4") (pinfunction "GND_K4") (pintype "passive"))
      (node (ref "Q1") (pin "K6") (pinfunction "GND_K6") (pintype "passive"))
      (node (ref "Q1") (pin "L1") (pinfunction "GND_L1") (pintype "passive"))
      (node (ref "Q1") (pin "L11") (pinfunction "GND_L11") (pintype "passive"))
      (node (ref "Q1") (pin "M8") (pinfunction "GND_M8") (pintype "passive"))
      (node (ref "Q1") (pin "N15") (pinfunction "GND_N15") (pintype "passive"))
      (node (ref "Q1") (pin "N5") (pinfunction "GND_N5") (pintype "passive"))
      (node (ref "Q1") (pin "P12") (pinfunction "GND_P12") (pintype "passive"))
      (node (ref "Q1") (pin "P2") (pinfunction "GND_P2") (pintype "passive"))
      (node (ref "Q1") (pin "R9") (pinfunction "GND_R9") (pintype "passive"))
      (node (ref "Q1") (pin "T16") (pinfunction "GND_T16") (pintype "passive"))
      (node (ref "Q1") (pin "T6") (pinfunction "GND_T6") (pintype "passive"))
      (node (ref "Q10") (pin "4") (pinfunction "GND_4") (pintype "passive"))
      (node (ref "Q11") (pin "4") (pinfunction "GND_4") (pintype "passive"))
      (node (ref "Q12") (pin "1") (pinfunction "GND_1") (pintype "passive"))
      (node (ref "Q2") (pin "10") (pinfunction "DGND_10") (pintype "passive"))
      (node (ref "Q2") (pin "24") (pinfunction "DGND_24") (pintype "passive"))
      (node (ref "Q2") (pin "3") (pinfunction "DGND_3") (pintype "passive"))
      (node (ref "Q2") (pin "32") (pinfunction "AGND_32") (pintype "passive"))
      (node (ref "Q2") (pin "37") (pinfunction "AGND_37") (pintype "passive"))
      (node (ref "Q2") (pin "43") (pinfunction "AGND_43") (pintype "passive"))
      (node (ref "Q2") (pin "57") (pinfunction "DGND_57") (pintype "passive"))
      (node (ref "Q4") (pin "64") (pinfunction "DGND_64") (pintype "passive"))
      (node (ref "Q4") (pin "65") (pinfunction "GND_65") (pintype "passive"))
      (node (ref "Q5") (pin "12") (pinfunction "VSSQ_12") (pintype "passive"))
      (node (ref "Q5") (pin "34") (pinfunction "VSS_34") (pintype "passive"))
      (node (ref "Q5") (pin "48") (pinfunction "VSS_48") (pintype "passive"))
      (node (ref "Q5") (pin "52") (pinfunction "VSSQ_52") (pintype "passive"))
      (node (ref "Q5") (pin "58") (pinfunction "VSSQ_58") (pintype "passive"))
      (node (ref "Q5") (pin "6") (pinfunction "VSSQ_6") (pintype "passive"))
      (node (ref "Q5") (pin "64") (pinfunction "VSSQ_64") (pintype "passive"))
      (node (ref "Q5") (pin "66") (pinfunction "VSS_66") (pintype "passive"))
      (node (ref "Q7") (pin "2") (pinfunction "GND_2") (pintype "passive"))
      (node (ref "Q8") (pin "4") (pinfunction "GND_4") (pintype "passive"))
      (node (ref "Q9") (pin "1") (pinfunction "GND_1") (pintype "passive"))
      (node (ref "R32") (pin "2") (pinfunction "2_2") (pintype "passive"))
      (node (ref "R34") (pin "2") (pinfunction "2_2") (pintype "passive"))
      (node (ref "R36") (pin "2") (pinfunction "2_2") (pintype "passive"))
    )
    (net (code "8") (name "HDAVDD") (class "Default")
      (node (ref "C114") (pin "1") (pinfunction "1_1") (pintype "passive"))
      (node (ref "C30") (pin "2") (pinfunction "2_2") (pintype "passive"))
      (node (ref "C31") (pin "2") (pinfunction "2_2") (pintype "passive"))
      (node (ref "L9") (pin "1") (pinfunction "1_1") (pintype "passive"))
      (node (ref "Q4") (pin "19") (pinfunction "AVDD_19") (pintype "passive"))
      (node (ref "Q4") (pin "23") (pinfunction "AVDD_23") (pintype "passive"))
      (node (ref "Q4") (pin "29") (pinfunction "AVDD_29") (pintype "passive"))
    )
    (net (code "9") (name "HDDVDD") (class "Default")
      (node (ref "C111") (pin "2") (pinfunction "2_2") (pintype "passive"))
      (node (ref "C26") (pin "1") (pinfunction "1_1") (pintype "passive"))
      (node (ref "C27") (pin "1") (pinfunction "1_1") (pintype "passive"))
      (node (ref "L7") (pin "1") (pinfunction "1_1") (pintype "passive"))
      (node (ref "Q4") (pin "1") (pinfunction "DVDD_1") (pintype "passive"))
      (node (ref "Q4") (pin "48") (pinfunction "DVDD_48") (pintype "passive"))
      (node (ref "Q4") (pin "49") (pinfunction "DVDD_49") (pintype "passive"))
    )
    (net (code "10") (name "HDPVDD") (class "Default")
      (node (ref "C112") (pin "2") (pinfunction "2_2") (pintype "passive"))
      (node (ref "C28") (pin "1") (pinfunction "1_1") (pintype "passive"))
      (node (ref "C29") (pin "1") (pinfunction "1_1") (pintype "passive"))
      (node (ref "L8") (pin "1") (pinfunction "1_1") (pintype "passive"))
      (node (ref "Q4") (pin "15") (pinfunction "PVDD_15") (pintype "passive"))
      (node (ref "Q4") (pin "16") (pinfunction "PVDD_16") (pintype "passive"))
      (node (ref "Q4") (pin "17") (pinfunction "PVDD_17") (pintype "passive"))
    )
    (net (code "11") (name "Net-(Q8-FB)") (class "Default")
      (node (ref "C106") (pin "2") (pinfunction "2_2") (pintype "passive"))
      (node (ref "Q8") (pin "5") (pinfunction "FB_5") (pintype "passive"))
      (node (ref "R31") (pin "1") (pinfunction "1_1") (pintype "passive"))
      (node (ref "R32") (pin "1") (pinfunction "1_1") (pintype "passive"))
    )
    (net (code "12") (name "Net-(Q8-SW)") (class "Default")
      (node (ref "L5") (pin "1") (pinfunction "1_1") (pintype "passive"))
      (node (ref "Q8") (pin "3") (pinfunction "SW_3") (pintype "passive"))
    )
    (net (code "13") (name "Net-(Q10-FB)") (class "Default")
      (node (ref "C110") (pin "2") (pinfunction "2_2") (pintype "passive"))
      (node (ref "Q10") (pin "5") (pinfunction "FB_5") (pintype "passive"))
      (node (ref "R33") (pin "1") (pinfunction "1_1") (pintype "passive"))
      (node (ref "R34") (pin "1") (pinfunction "1_1") (pintype "passive"))
    )
    (net (code "14") (name "Net-(Q10-SW)") (class "Default")
      (node (ref "L6") (pin "1") (pinfunction "1_1") (pintype "passive"))
      (node (ref "Q10") (pin "3") (pinfunction "SW_3") (pintype "passive"))
    )
    (net (code "15") (name "Net-(Q11-FB)") (class "Default")
      (node (ref "C115") (pin "2") (pinfunction "2_2") (pintype "passive"))
      (node (ref "Q11") (pin "5") (pinfunction "FB_5") (pintype "passive"))
      (node (ref "R35") (pin "1") (pinfunction "1_1") (pintype "passive"))
      (node (ref "R36") (pin "1") (pinfunction "1_1") (pintype "passive"))
    )
    (net (code "16") (name "Net-(Q11-SW)") (class "Default")
      (node (ref "L10") (pin "1") (pinfunction "1_1") (pintype "passive"))
      (node (ref "Q11") (pin "3") (pinfunction "SW_3") (pintype "passive"))
    )
    (net (code "17") (name "P1V8") (class "Default")
      (node (ref "C105") (pin "1") (pinfunction "1_1") (pintype "passive"))
      (node (ref "C25") (pin "2") (pinfunction "2_2") (pintype "passive"))
      (node (ref "C92") (pin "2") (pinfunction "2_2") (pintype "passive"))
      (node (ref "Q2") (pin "31") (pinfunction "PVDD_31") (pintype "passive"))
      (node (ref "Q7") (pin "5") (pinfunction "VOUT_5") (pintype "passive"))
    )
    (net (code "18") (name "unconnected-(Q9-VOUT-Pad2)") (class "Default")
      (node (ref "Q9") (pin "2") (pinfunction "VOUT_2") (pintype "passive"))
    )
  )
)
